# Tractive_System_Active_Light_rev1.net
KiCad netlist of a schematic drawn in EAGLE
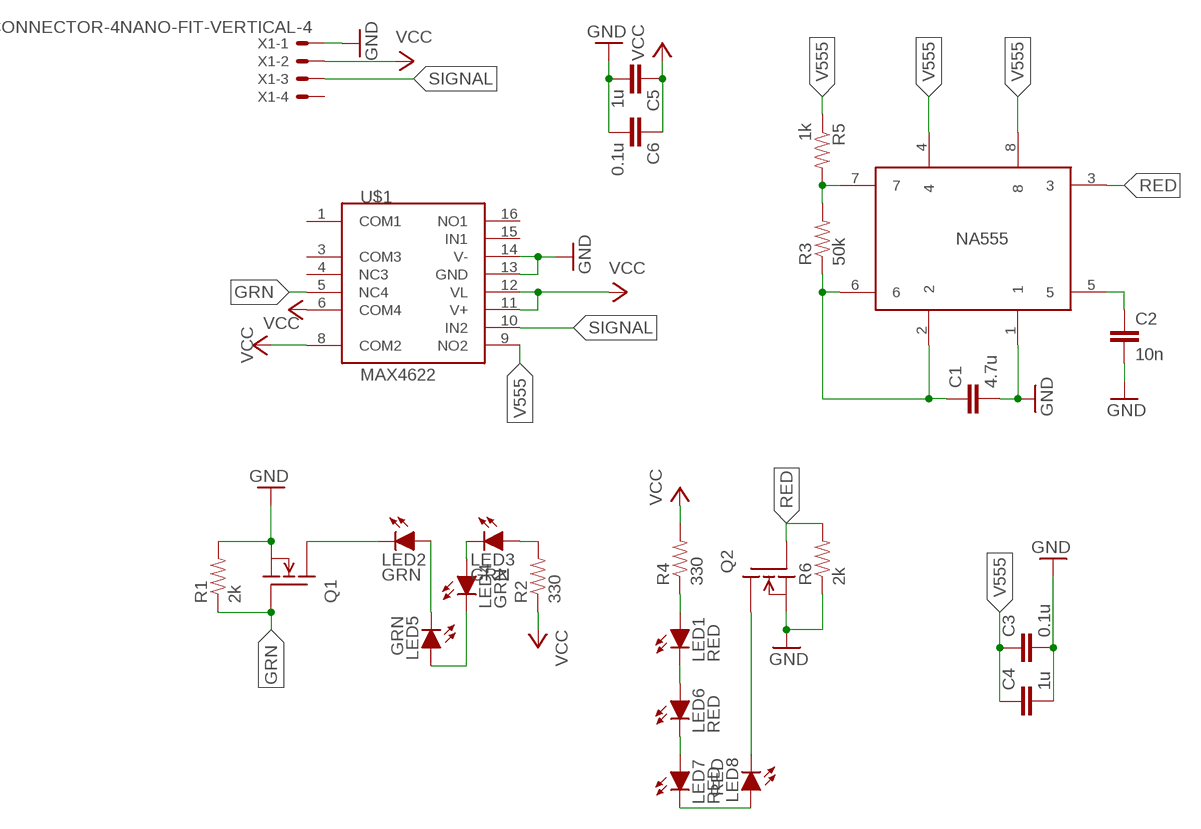
[diagram p0: schematic, sheet 1]

(export (version "E")
  (design (tool "Eeschema 10.0.6"))
  (components
    (comp (ref "C1")
      (value "4.7u")
      (footprint "eagle-import:0603-CAP")
      (libsource (lib "eagle-import") (part "CAP0603-CAP"))
    )
    (comp (ref "C2")
      (value "10n")
      (footprint "eagle-import:0603-CAP")
      (libsource (lib "eagle-import") (part "CAP0603-CAP"))
    )
    (comp (ref "C3")
      (value "0.1u")
      (footprint "eagle-import:0603-CAP")
      (libsource (lib "eagle-import") (part "CAP0603-CAP"))
    )
    (comp (ref "C4")
      (value "1u")
      (footprint "eagle-import:0603-CAP")
      (libsource (lib "eagle-import") (part "CAP0603-CAP"))
    )
    (comp (ref "C5")
      (value "1u")
      (footprint "eagle-import:0603-CAP")
      (libsource (lib "eagle-import") (part "CAP0603-CAP"))
    )
    (comp (ref "C6")
      (value "0.1u")
      (footprint "eagle-import:0603-CAP")
      (libsource (lib "eagle-import") (part "CAP0603-CAP"))
    )
    (comp (ref "LED1")
      (value "RED")
      (footprint "eagle-import:XP-E2")
      (libsource (lib "eagle-import") (part "XP-E2"))
    )
    (comp (ref "LED2")
      (value "GRN")
      (footprint "eagle-import:XP-E2")
      (libsource (lib "eagle-import") (part "XP-E2"))
    )
    (comp (ref "LED3")
      (value "GRN")
      (footprint "eagle-import:XP-E2")
      (libsource (lib "eagle-import") (part "XP-E2"))
    )
    (comp (ref "LED4")
      (value "GRN")
      (footprint "eagle-import:XP-E2")
      (libsource (lib "eagle-import") (part "XP-E2"))
    )
    (comp (ref "LED5")
      (value "GRN")
      (footprint "eagle-import:XP-E2")
      (libsource (lib "eagle-import") (part "XP-E2"))
    )
    (comp (ref "LED6")
      (value "RED")
      (footprint "eagle-import:XP-E2")
      (libsource (lib "eagle-import") (part "XP-E2"))
    )
    (comp (ref "LED7")
      (value "RED")
      (footprint "eagle-import:XP-E2")
      (libsource (lib "eagle-import") (part "XP-E2"))
    )
    (comp (ref "LED8")
      (value "RED")
      (footprint "eagle-import:XP-E2")
      (libsource (lib "eagle-import") (part "XP-E2"))
    )
    (comp (ref "NA555")
      (value "NA555SO-8")
      (footprint "eagle-import:SO8")
      (libsource (lib "eagle-import") (part "NA555SO-8"))
    )
    (comp (ref "Q1")
      (value "DMG3406LSOT")
      (footprint "eagle-import:SOT23")
      (libsource (lib "eagle-import") (part "DMG3406LSOT"))
    )
    (comp (ref "Q2")
      (value "DMG3406LSOT")
      (footprint "eagle-import:SOT23")
      (libsource (lib "eagle-import") (part "DMG3406LSOT"))
    )
    (comp (ref "R1")
      (value "2k")
      (footprint "eagle-import:0603-RES")
      (libsource (lib "eagle-import") (part "RESISTOR0603-RES"))
    )
    (comp (ref "R2")
      (value "330")
      (footprint "eagle-import:0603-RES")
      (libsource (lib "eagle-import") (part "RESISTOR0603-RES"))
    )
    (comp (ref "R3")
      (value "50k")
      (footprint "eagle-import:0603-RES")
      (libsource (lib "eagle-import") (part "RESISTOR0603-RES"))
    )
    (comp (ref "R4")
      (value "330")
      (footprint "eagle-import:0603-RES")
      (libsource (lib "eagle-import") (part "RESISTOR0603-RES"))
    )
    (comp (ref "R5")
      (value "1k")
      (footprint "eagle-import:0603-RES")
      (libsource (lib "eagle-import") (part "RESISTOR0603-RES"))
    )
    (comp (ref "R6")
      (value "2k")
      (footprint "eagle-import:0603-RES")
      (libsource (lib "eagle-import") (part "RESISTOR0603-RES"))
    )
    (comp (ref "U$1")
      (value "MAX4622")
      (footprint "eagle-import:SO16")
      (libsource (lib "eagle-import") (part "MAX4622"))
    )
    (comp (ref "X1")
      (value "CONNECTOR-4NANO-FIT-VERTICAL-4")
      (footprint "eagle-import:NANO-FIT_VERTICAL-4")
      (libsource (lib "eagle-import") (part "CONNECTOR-4NANO-FIT-VERTICAL-4"))
    )
  )
  (nets
    (net (code "1") (name "GND") (class "Default")
      (node (ref "C1") (pin "2") (pinfunction "2_2") (pintype "passive"))
      (node (ref "C2") (pin "2") (pinfunction "2_2") (pintype "passive"))
      (node (ref "C3") (pin "2") (pinfunction "2_2") (pintype "passive"))
      (node (ref "C4") (pin "2") (pinfunction "2_2") (pintype "passive"))
      (node (ref "C5") (pin "2") (pinfunction "2_2") (pintype "passive"))
      (node (ref "C6") (pin "2") (pinfunction "2_2") (pintype "passive"))
      (node (ref "NA555") (pin "1") (pinfunction "1_1") (pintype "bidirectional"))
      (node (ref "Q1") (pin "2") (pinfunction "S_2") (pintype "passive"))
      (node (ref "Q2") (pin "2") (pinfunction "S_2") (pintype "passive"))
      (node (ref "R1") (pin "2") (pinfunction "2_2") (pintype "passive"))
      (node (ref "R6") (pin "1") (pinfunction "1_1") (pintype "passive"))
      (node (ref "U$1") (pin "13") (pinfunction "GND_13") (pintype "bidirectional"))
      (node (ref "U$1") (pin "14") (pinfunction "V-_14") (pintype "bidirectional"))
      (node (ref "X1") (pin "P$1") (pinfunction "S_P$1") (pintype "passive"))
    )
    (net (code "2") (name "GRN") (class "Default")
      (node (ref "Q1") (pin "1") (pinfunction "G_1") (pintype "passive"))
      (node (ref "R1") (pin "1") (pinfunction "1_1") (pintype "passive"))
      (node (ref "U$1") (pin "5") (pinfunction "NC4_5") (pintype "bidirectional"))
    )
    (net (code "3") (name "Net-(C1-Pad1)") (class "Default")
      (node (ref "C1") (pin "1") (pinfunction "1_1") (pintype "passive"))
      (node (ref "NA555") (pin "2") (pinfunction "2_2") (pintype "bidirectional"))
      (node (ref "NA555") (pin "6") (pinfunction "6_6") (pintype "bidirectional"))
      (node (ref "R3") (pin "1") (pinfunction "1_1") (pintype "passive"))
    )
    (net (code "4") (name "Net-(C2-Pad1)") (class "Default")
      (node (ref "C2") (pin "1") (pinfunction "1_1") (pintype "passive"))
      (node (ref "NA555") (pin "5") (pinfunction "5_5") (pintype "bidirectional"))
    )
    (net (code "5") (name "Net-(LED1-PadA)") (class "Default")
      (node (ref "LED1") (pin "A") (pinfunction "A_A") (pintype "passive"))
      (node (ref "R4") (pin "1") (pinfunction "1_1") (pintype "passive"))
    )
    (net (code "6") (name "Net-(LED1-PadC)") (class "Default")
      (node (ref "LED1") (pin "C") (pinfunction "C_C") (pintype "passive"))
      (node (ref "LED6") (pin "A") (pinfunction "A_A") (pintype "passive"))
    )
    (net (code "7") (name "Net-(LED2-PadA)") (class "Default")
      (node (ref "LED2") (pin "A") (pinfunction "A_A") (pintype "passive"))
      (node (ref "LED5") (pin "C") (pinfunction "C_C") (pintype "passive"))
    )
    (net (code "8") (name "Net-(LED3-PadA)") (class "Default")
      (node (ref "LED3") (pin "A") (pinfunction "A_A") (pintype "passive"))
      (node (ref "R2") (pin "2") (pinfunction "2_2") (pintype "passive"))
    )
    (net (code "9") (name "Net-(LED3-PadC)") (class "Default")
      (node (ref "LED3") (pin "C") (pinfunction "C_C") (pintype "passive"))
      (node (ref "LED4") (pin "A") (pinfunction "A_A") (pintype "passive"))
    )
    (net (code "10") (name "Net-(LED4-PadC)") (class "Default")
      (node (ref "LED4") (pin "C") (pinfunction "C_C") (pintype "passive"))
      (node (ref "LED5") (pin "A") (pinfunction "A_A") (pintype "passive"))
    )
    (net (code "11") (name "Net-(LED6-PadC)") (class "Default")
      (node (ref "LED6") (pin "C") (pinfunction "C_C") (pintype "passive"))
      (node (ref "LED7") (pin "A") (pinfunction "A_A") (pintype "passive"))
    )
    (net (code "12") (name "Net-(LED7-PadC)") (class "Default")
      (node (ref "LED7") (pin "C") (pinfunction "C_C") (pintype "passive"))
      (node (ref "LED8") (pin "A") (pinfunction "A_A") (pintype "passive"))
    )
    (net (code "13") (name "Net-(NA555-Pad7)") (class "Default")
      (node (ref "NA555") (pin "7") (pinfunction "7_7") (pintype "bidirectional"))
      (node (ref "R3") (pin "2") (pinfunction "2_2") (pintype "passive"))
      (node (ref "R5") (pin "2") (pinfunction "2_2") (pintype "passive"))
    )
    (net (code "14") (name "Net-(Q1-D)") (class "Default")
      (node (ref "LED2") (pin "C") (pinfunction "C_C") (pintype "passive"))
      (node (ref "Q1") (pin "3") (pinfunction "D_3") (pintype "passive"))
    )
    (net (code "15") (name "Net-(Q2-D)") (class "Default")
      (node (ref "LED8") (pin "C") (pinfunction "C_C") (pintype "passive"))
      (node (ref "Q2") (pin "3") (pinfunction "D_3") (pintype "passive"))
    )
    (net (code "16") (name "RED") (class "Default")
      (node (ref "NA555") (pin "3") (pinfunction "3_3") (pintype "bidirectional"))
      (node (ref "Q2") (pin "1") (pinfunction "G_1") (pintype "passive"))
      (node (ref "R6") (pin "2") (pinfunction "2_2") (pintype "passive"))
    )
    (net (code "17") (name "SIGNAL") (class "Default")
      (node (ref "U$1") (pin "10") (pinfunction "IN2_10") (pintype "bidirectional"))
      (node (ref "X1") (pin "P$3") (pinfunction "S_P$3") (pintype "passive"))
    )
    (net (code "18") (name "V555") (class "Default")
      (node (ref "C3") (pin "1") (pinfunction "1_1") (pintype "passive"))
      (node (ref "C4") (pin "1") (pinfunction "1_1") (pintype "passive"))
      (node (ref "NA555") (pin "4") (pinfunction "4_4") (pintype "bidirectional"))
      (node (ref "NA555") (pin "8") (pinfunction "8_8") (pintype "bidirectional"))
      (node (ref "R5") (pin "1") (pinfunction "1_1") (pintype "passive"))
      (node (ref "U$1") (pin "9") (pinfunction "NO2_9") (pintype "bidirectional"))
    )
    (net (code "19") (name "VCC") (class "Default")
      (node (ref "C5") (pin "1") (pinfunction "1_1") (pintype "passive"))
      (node (ref "C6") (pin "1") (pinfunction "1_1") (pintype "passive"))
      (node (ref "R2") (pin "1") (pinfunction "1_1") (pintype "passive"))
      (node (ref "R4") (pin "2") (pinfunction "2_2") (pintype "passive"))
      (node (ref "U$1") (pin "11") (pinfunction "V+_11") (pintype "bidirectional"))
      (node (ref "U$1") (pin "12") (pinfunction "VL_12") (pintype "bidirectional"))
      (node (ref "U$1") (pin "6") (pinfunction "COM4_6") (pintype "bidirectional"))
      (node (ref "U$1") (pin "8") (pinfunction "COM2_8") (pintype "bidirectional"))
      (node (ref "X1") (pin "P$2") (pinfunction "S_P$2") (pintype "passive"))
    )
    (net (code "20") (name "unconnected-(U$1-COM1-Pad1)") (class "Default")
      (node (ref "U$1") (pin "1") (pinfunction "COM1_1") (pintype "bidirectional"))
    )
    (net (code "21") (name "unconnected-(U$1-COM3-Pad3)") (class "Default")
      (node (ref "U$1") (pin "3") (pinfunction "COM3_3") (pintype "bidirectional"))
    )
    (net (code "22") (name "unconnected-(U$1-IN1-Pad15)") (class "Default")
      (node (ref "U$1") (pin "15") (pinfunction "IN1_15") (pintype "bidirectional"))
    )
    (net (code "23") (name "unconnected-(U$1-NC3-Pad4)") (class "Default")
      (node (ref "U$1") (pin "4") (pinfunction "NC3_4") (pintype "bidirectional"))
    )
    (net (code "24") (name "unconnected-(U$1-NO1-Pad16)") (class "Default")
      (node (ref "U$1") (pin "16") (pinfunction "NO1_16") (pintype "bidirectional"))
    )
    (net (code "25") (name "unconnected-(X1D-S-PadP$4)") (class "Default")
      (node (ref "X1") (pin "P$4") (pinfunction "S_P$4") (pintype "passive"))
    )
  )
)
